# Group_08_alternative.net
KiCad netlist of a schematic drawn in EAGLE
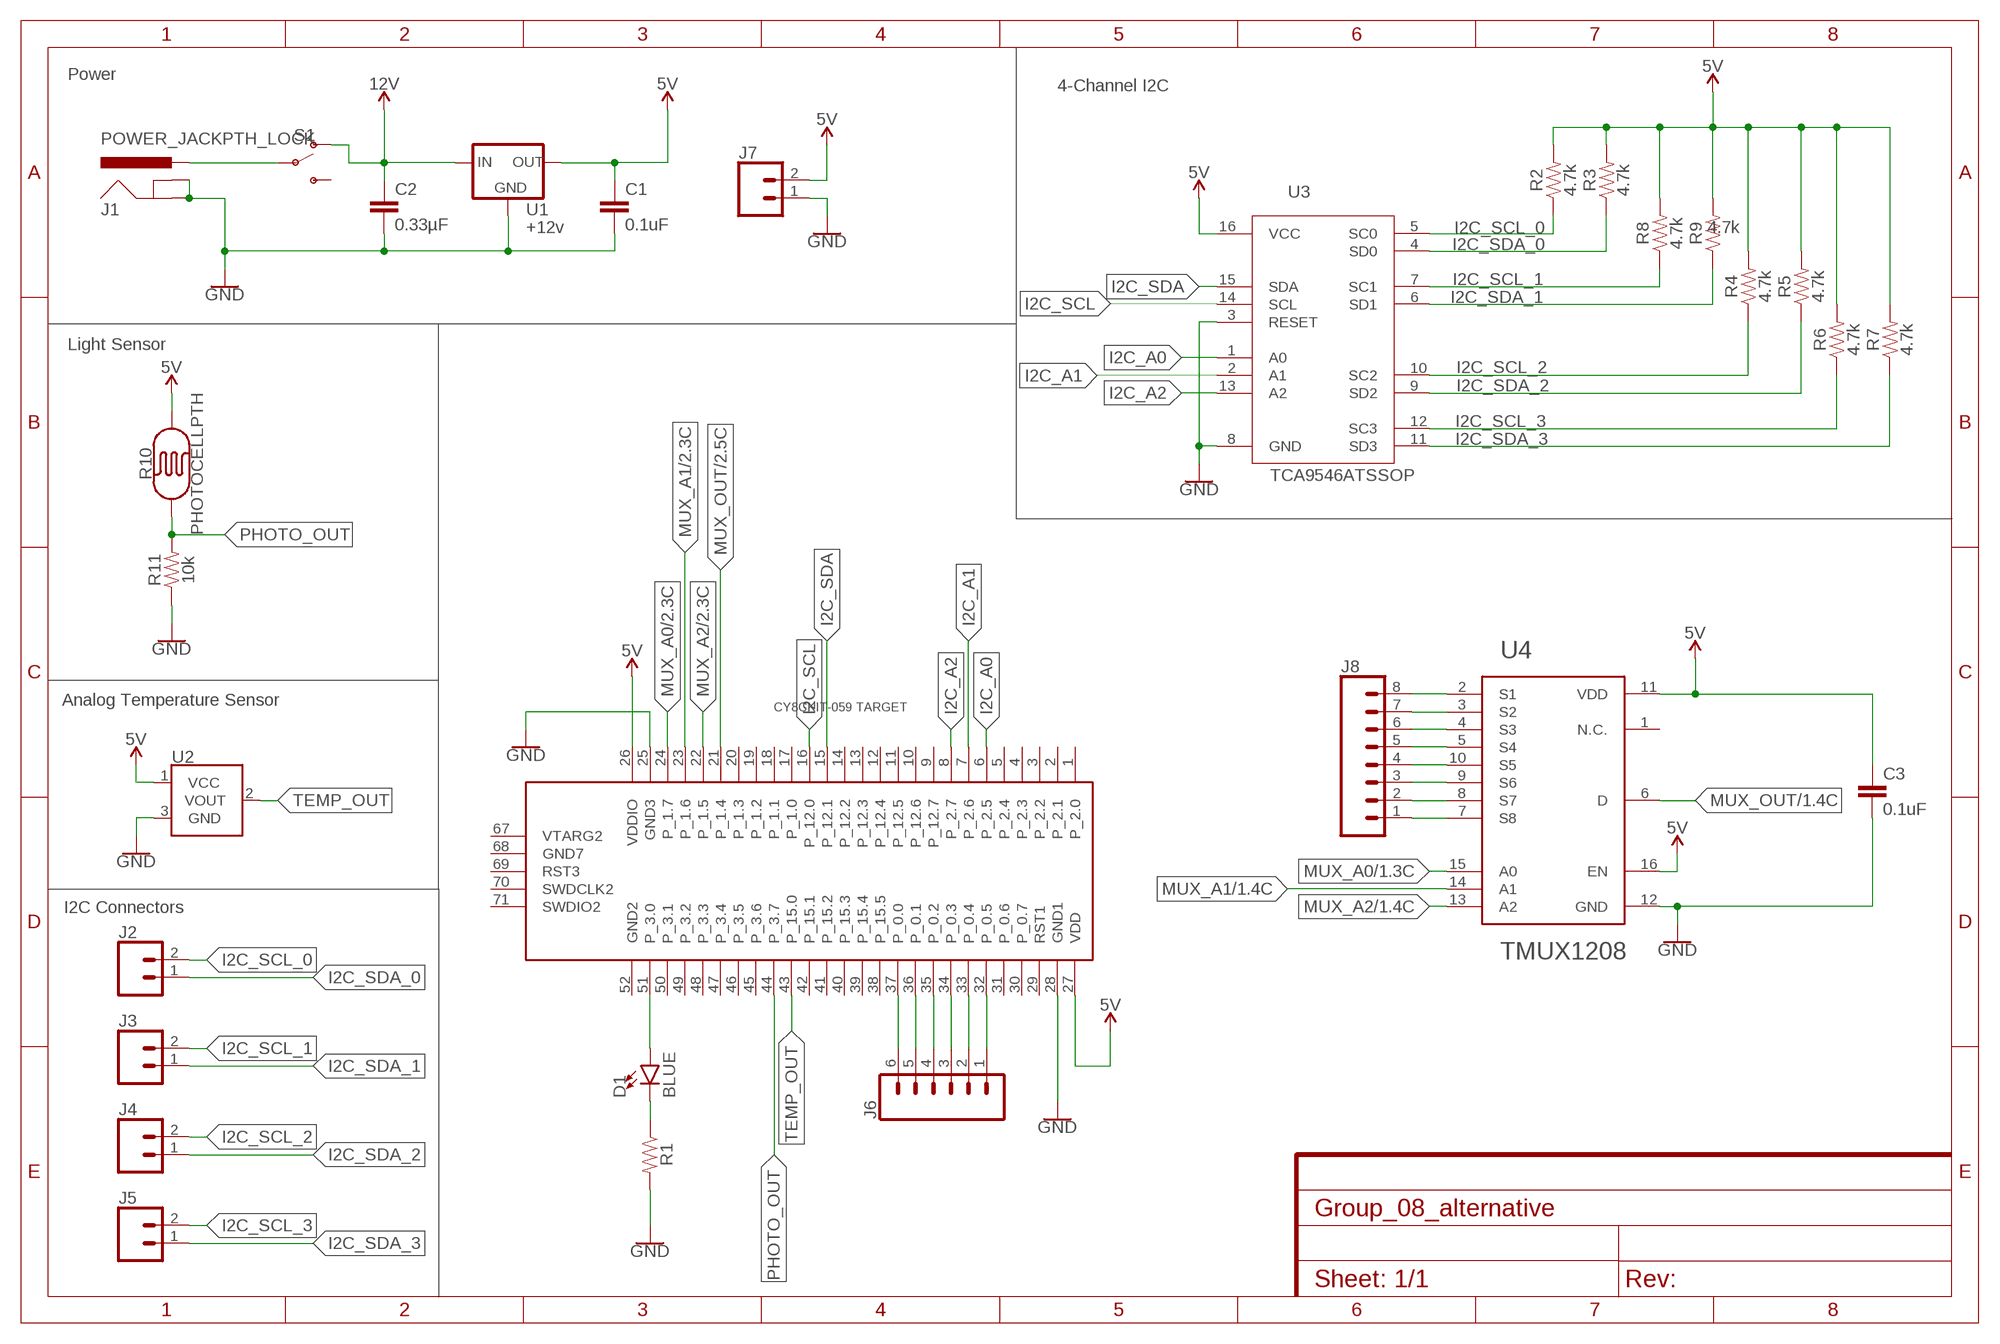
[diagram p0: schematic, sheet 1]

(export (version "E")
  (design (tool "Eeschema 10.0.6"))
  (components
    (comp (ref "C1")
      (value "0.1uF")
      (footprint "eagle-import:CAP-PTH-SMALL-KIT")
      (libsource (lib "eagle-import") (part "0.1UF-KIT-EZ-50V-20%"))
    )
    (comp (ref "C2")
      (value "0.33µF")
      (footprint "eagle-import:0805")
      (libsource (lib "eagle-import") (part "0.33UF/330NF-0805-50V-10%"))
    )
    (comp (ref "C3")
      (value "0.1uF")
      (footprint "eagle-import:CAP-PTH-SMALL-KIT")
      (libsource (lib "eagle-import") (part "0.1UF-KIT-EZ-50V-20%"))
    )
    (comp (ref "CY8CKIT059-TARGET")
      (value "CY8CKIT-059_TARGET")
      (footprint "eagle-import:CY8CKIT-059_TARGET")
      (libsource (lib "eagle-import") (part "CY8CKIT-059_TARGET"))
    )
    (comp (ref "D1")
      (value "BLUE")
      (footprint "eagle-import:LED-1206")
      (libsource (lib "eagle-import") (part "LED-BLUE1206"))
    )
    (comp (ref "J1")
      (value "POWER_JACKPTH_LOCK")
      (footprint "eagle-import:POWER_JACK_PTH_LOCK")
      (libsource (lib "eagle-import") (part "POWER_JACKPTH_LOCK"))
    )
    (comp (ref "J2")
      (value "CONN_02")
      (footprint "eagle-import:1X02")
      (libsource (lib "eagle-import") (part "CONN_02"))
    )
    (comp (ref "J3")
      (value "CONN_02")
      (footprint "eagle-import:1X02")
      (libsource (lib "eagle-import") (part "CONN_02"))
    )
    (comp (ref "J4")
      (value "CONN_02")
      (footprint "eagle-import:1X02")
      (libsource (lib "eagle-import") (part "CONN_02"))
    )
    (comp (ref "J5")
      (value "CONN_02")
      (footprint "eagle-import:1X02")
      (libsource (lib "eagle-import") (part "CONN_02"))
    )
    (comp (ref "J6")
      (value "CONN_06LOCK")
      (footprint "eagle-import:1X06_LOCK")
      (libsource (lib "eagle-import") (part "CONN_06LOCK"))
    )
    (comp (ref "J7")
      (value "CONN_02")
      (footprint "eagle-import:1X02")
      (libsource (lib "eagle-import") (part "CONN_02"))
    )
    (comp (ref "J8")
      (value "CONN_08LOCK")
      (footprint "eagle-import:1X08_LOCK")
      (libsource (lib "eagle-import") (part "CONN_08LOCK"))
    )
    (comp (ref "R1")
      (value "RESISTORAXIAL-0.3")
      (footprint "eagle-import:AXIAL-0.3")
      (libsource (lib "eagle-import") (part "RESISTORAXIAL-0.3"))
    )
    (comp (ref "R2")
      (value "4.7k")
      (footprint "eagle-import:0603")
      (libsource (lib "eagle-import") (part "4.7KOHM-0603-1/10W-1%"))
    )
    (comp (ref "R3")
      (value "4.7k")
      (footprint "eagle-import:0603")
      (libsource (lib "eagle-import") (part "4.7KOHM-0603-1/10W-1%"))
    )
    (comp (ref "R4")
      (value "4.7k")
      (footprint "eagle-import:0603")
      (libsource (lib "eagle-import") (part "4.7KOHM-0603-1/10W-1%"))
    )
    (comp (ref "R5")
      (value "4.7k")
      (footprint "eagle-import:0603")
      (libsource (lib "eagle-import") (part "4.7KOHM-0603-1/10W-1%"))
    )
    (comp (ref "R6")
      (value "4.7k")
      (footprint "eagle-import:0603")
      (libsource (lib "eagle-import") (part "4.7KOHM-0603-1/10W-1%"))
    )
    (comp (ref "R7")
      (value "4.7k")
      (footprint "eagle-import:0603")
      (libsource (lib "eagle-import") (part "4.7KOHM-0603-1/10W-1%"))
    )
    (comp (ref "R8")
      (value "4.7k")
      (footprint "eagle-import:0603")
      (libsource (lib "eagle-import") (part "4.7KOHM-0603-1/10W-1%"))
    )
    (comp (ref "R9")
      (value "4.7k")
      (footprint "eagle-import:0603")
      (libsource (lib "eagle-import") (part "4.7KOHM-0603-1/10W-1%"))
    )
    (comp (ref "R10")
      (value "PHOTOCELLPTH")
      (footprint "eagle-import:PHOTOCELL")
      (libsource (lib "eagle-import") (part "PHOTOCELLPTH"))
    )
    (comp (ref "R11")
      (value "10k")
      (footprint "eagle-import:0603")
      (libsource (lib "eagle-import") (part "10KOHM-0603-1/10W-1%"))
    )
    (comp (ref "S1")
      (value "SWITCH-SPDT-PTH-11.6X4.0MM")
      (footprint "eagle-import:SWITCH_SPDT_PTH_11.6X4.0MM")
      (libsource (lib "eagle-import") (part "SWITCH-SPDT-PTH-11.6X4.0MM"))
    )
    (comp (ref "U1")
      (value "+12v")
      (footprint "eagle-import:TO-252")
      (libsource (lib "eagle-import") (part "V_REG_78XX7812"))
    )
    (comp (ref "U2")
      (value "TMP36GT9")
      (footprint "eagle-import:TO-92")
      (libsource (lib "eagle-import") (part "TMP36GT9"))
    )
    (comp (ref "U3")
      (value "TCA9546ATSSOP")
      (footprint "eagle-import:TSSOP16")
      (libsource (lib "eagle-import") (part "TCA9546ATSSOP"))
    )
    (comp (ref "U4")
      (value "TMUX1208")
      (footprint "eagle-import:QFN16")
      (libsource (lib "eagle-import") (part "TMUX1208"))
    )
  )
  (nets
    (net (code "1") (name "5V") (class "Default")
      (node (ref "C1") (pin "1") (pinfunction "1_1") (pintype "passive"))
      (node (ref "C3") (pin "1") (pinfunction "1_1") (pintype "passive"))
      (node (ref "CY8CKIT059-TARGET") (pin "26") (pinfunction "VDDIO_26") (pintype "bidirectional"))
      (node (ref "CY8CKIT059-TARGET") (pin "27") (pinfunction "VDD_27") (pintype "bidirectional"))
      (node (ref "J7") (pin "2") (pinfunction "2_2") (pintype "passive"))
      (node (ref "R10") (pin "2") (pinfunction "P$2_2") (pintype "bidirectional"))
      (node (ref "R2") (pin "2") (pinfunction "2_2") (pintype "passive"))
      (node (ref "R3") (pin "2") (pinfunction "2_2") (pintype "passive"))
      (node (ref "R4") (pin "2") (pinfunction "2_2") (pintype "passive"))
      (node (ref "R5") (pin "2") (pinfunction "2_2") (pintype "passive"))
      (node (ref "R6") (pin "2") (pinfunction "2_2") (pintype "passive"))
      (node (ref "R7") (pin "2") (pinfunction "2_2") (pintype "passive"))
      (node (ref "R8") (pin "2") (pinfunction "2_2") (pintype "passive"))
      (node (ref "R9") (pin "2") (pinfunction "2_2") (pintype "passive"))
      (node (ref "U1") (pin "2") (pinfunction "OUT_2") (pintype "passive"))
      (node (ref "U2") (pin "1") (pinfunction "VCC_1") (pintype "bidirectional"))
      (node (ref "U3") (pin "16") (pinfunction "VCC_16") (pintype "bidirectional"))
      (node (ref "U4") (pin "11") (pinfunction "VDD_11") (pintype "bidirectional"))
      (node (ref "U4") (pin "16") (pinfunction "EN_16") (pintype "bidirectional"))
    )
    (net (code "2") (name "12V") (class "Default")
      (node (ref "C2") (pin "1") (pinfunction "1_1") (pintype "passive"))
      (node (ref "S1") (pin "1") (pinfunction "O_1") (pintype "passive"))
      (node (ref "U1") (pin "1") (pinfunction "IN_1") (pintype "input"))
    )
    (net (code "3") (name "GND") (class "Default")
      (node (ref "C1") (pin "2") (pinfunction "2_2") (pintype "passive"))
      (node (ref "C2") (pin "2") (pinfunction "2_2") (pintype "passive"))
      (node (ref "C3") (pin "2") (pinfunction "2_2") (pintype "passive"))
      (node (ref "CY8CKIT059-TARGET") (pin "25") (pinfunction "GND3_25") (pintype "bidirectional"))
      (node (ref "CY8CKIT059-TARGET") (pin "28") (pinfunction "GND1_28") (pintype "bidirectional"))
      (node (ref "J1") (pin "GND") (pinfunction "GND_GND") (pintype "bidirectional"))
      (node (ref "J1") (pin "GNDBREAK") (pinfunction "GNDBREAK_GNDBREAK") (pintype "bidirectional"))
      (node (ref "J7") (pin "1") (pinfunction "1_1") (pintype "passive"))
      (node (ref "R1") (pin "P$2") (pinfunction "2_P$2") (pintype "passive"))
      (node (ref "R11") (pin "1") (pinfunction "1_1") (pintype "passive"))
      (node (ref "U1") (pin "3") (pinfunction "GND_3") (pintype "input"))
      (node (ref "U2") (pin "3") (pinfunction "GND_3") (pintype "bidirectional"))
      (node (ref "U3") (pin "3") (pinfunction "RESET_3") (pintype "bidirectional"))
      (node (ref "U3") (pin "8") (pinfunction "GND_8") (pintype "bidirectional"))
      (node (ref "U4") (pin "12") (pinfunction "GND_12") (pintype "bidirectional"))
    )
    (net (code "4") (name "I2C_A0") (class "Default")
      (node (ref "CY8CKIT059-TARGET") (pin "6") (pinfunction "P_2.5_6") (pintype "bidirectional"))
      (node (ref "U3") (pin "1") (pinfunction "A0_1") (pintype "bidirectional"))
    )
    (net (code "5") (name "I2C_A1") (class "Default")
      (node (ref "CY8CKIT059-TARGET") (pin "7") (pinfunction "P_2.6_7") (pintype "bidirectional"))
      (node (ref "U3") (pin "2") (pinfunction "A1_2") (pintype "bidirectional"))
    )
    (net (code "6") (name "I2C_A2") (class "Default")
      (node (ref "CY8CKIT059-TARGET") (pin "8") (pinfunction "P_2.7_8") (pintype "bidirectional"))
      (node (ref "U3") (pin "13") (pinfunction "A2_13") (pintype "bidirectional"))
    )
    (net (code "7") (name "I2C_SCL") (class "Default")
      (node (ref "CY8CKIT059-TARGET") (pin "16") (pinfunction "P_12.0_16") (pintype "bidirectional"))
      (node (ref "U3") (pin "14") (pinfunction "SCL_14") (pintype "bidirectional"))
    )
    (net (code "8") (name "I2C_SCL_0") (class "Default")
      (node (ref "J2") (pin "2") (pinfunction "2_2") (pintype "passive"))
      (node (ref "R2") (pin "1") (pinfunction "1_1") (pintype "passive"))
      (node (ref "U3") (pin "5") (pinfunction "SC0_5") (pintype "bidirectional"))
    )
    (net (code "9") (name "I2C_SCL_1") (class "Default")
      (node (ref "J3") (pin "2") (pinfunction "2_2") (pintype "passive"))
      (node (ref "R8") (pin "1") (pinfunction "1_1") (pintype "passive"))
      (node (ref "U3") (pin "7") (pinfunction "SC1_7") (pintype "bidirectional"))
    )
    (net (code "10") (name "I2C_SCL_2") (class "Default")
      (node (ref "J4") (pin "2") (pinfunction "2_2") (pintype "passive"))
      (node (ref "R4") (pin "1") (pinfunction "1_1") (pintype "passive"))
      (node (ref "U3") (pin "10") (pinfunction "SC2_10") (pintype "bidirectional"))
    )
    (net (code "11") (name "I2C_SCL_3") (class "Default")
      (node (ref "J5") (pin "2") (pinfunction "2_2") (pintype "passive"))
      (node (ref "R6") (pin "1") (pinfunction "1_1") (pintype "passive"))
      (node (ref "U3") (pin "12") (pinfunction "SC3_12") (pintype "bidirectional"))
    )
    (net (code "12") (name "I2C_SDA") (class "Default")
      (node (ref "CY8CKIT059-TARGET") (pin "15") (pinfunction "P_12.1_15") (pintype "bidirectional"))
      (node (ref "U3") (pin "15") (pinfunction "SDA_15") (pintype "bidirectional"))
    )
    (net (code "13") (name "I2C_SDA_0") (class "Default")
      (node (ref "J2") (pin "1") (pinfunction "1_1") (pintype "passive"))
      (node (ref "R3") (pin "1") (pinfunction "1_1") (pintype "passive"))
      (node (ref "U3") (pin "4") (pinfunction "SD0_4") (pintype "bidirectional"))
    )
    (net (code "14") (name "I2C_SDA_1") (class "Default")
      (node (ref "J3") (pin "1") (pinfunction "1_1") (pintype "passive"))
      (node (ref "R9") (pin "1") (pinfunction "1_1") (pintype "passive"))
      (node (ref "U3") (pin "6") (pinfunction "SD1_6") (pintype "bidirectional"))
    )
    (net (code "15") (name "I2C_SDA_2") (class "Default")
      (node (ref "J4") (pin "1") (pinfunction "1_1") (pintype "passive"))
      (node (ref "R5") (pin "1") (pinfunction "1_1") (pintype "passive"))
      (node (ref "U3") (pin "9") (pinfunction "SD2_9") (pintype "bidirectional"))
    )
    (net (code "16") (name "I2C_SDA_3") (class "Default")
      (node (ref "J5") (pin "1") (pinfunction "1_1") (pintype "passive"))
      (node (ref "R7") (pin "1") (pinfunction "1_1") (pintype "passive"))
      (node (ref "U3") (pin "11") (pinfunction "SD3_11") (pintype "bidirectional"))
    )
    (net (code "17") (name "MUX_A0{slash}1.3C") (class "Default")
      (node (ref "U4") (pin "15") (pinfunction "A0_15") (pintype "bidirectional"))
    )
    (net (code "18") (name "MUX_A0{slash}2.3C") (class "Default")
      (node (ref "CY8CKIT059-TARGET") (pin "24") (pinfunction "P_1.7_24") (pintype "bidirectional"))
    )
    (net (code "19") (name "MUX_A1{slash}1.4C") (class "Default")
      (node (ref "U4") (pin "14") (pinfunction "A1_14") (pintype "bidirectional"))
    )
    (net (code "20") (name "MUX_A1{slash}2.3C") (class "Default")
      (node (ref "CY8CKIT059-TARGET") (pin "23") (pinfunction "P_1.6_23") (pintype "bidirectional"))
    )
    (net (code "21") (name "MUX_A2{slash}1.4C") (class "Default")
      (node (ref "U4") (pin "13") (pinfunction "A2_13") (pintype "bidirectional"))
    )
    (net (code "22") (name "MUX_A2{slash}2.3C") (class "Default")
      (node (ref "CY8CKIT059-TARGET") (pin "22") (pinfunction "P_1.5_22") (pintype "bidirectional"))
    )
    (net (code "23") (name "MUX_OUT{slash}1.4C") (class "Default")
      (node (ref "U4") (pin "6") (pinfunction "D_6") (pintype "bidirectional"))
    )
    (net (code "24") (name "MUX_OUT{slash}2.5C") (class "Default")
      (node (ref "CY8CKIT059-TARGET") (pin "21") (pinfunction "P_1.4_21") (pintype "bidirectional"))
    )
    (net (code "25") (name "Net-(CY8CKIT059-TARGET-P_0.0)") (class "Default")
      (node (ref "CY8CKIT059-TARGET") (pin "37") (pinfunction "P_0.0_37") (pintype "bidirectional"))
      (node (ref "J6") (pin "6") (pinfunction "6_6") (pintype "passive"))
    )
    (net (code "26") (name "Net-(CY8CKIT059-TARGET-P_0.1)") (class "Default")
      (node (ref "CY8CKIT059-TARGET") (pin "36") (pinfunction "P_0.1_36") (pintype "bidirectional"))
      (node (ref "J6") (pin "5") (pinfunction "5_5") (pintype "passive"))
    )
    (net (code "27") (name "Net-(CY8CKIT059-TARGET-P_0.2)") (class "Default")
      (node (ref "CY8CKIT059-TARGET") (pin "35") (pinfunction "P_0.2_35") (pintype "bidirectional"))
      (node (ref "J6") (pin "4") (pinfunction "4_4") (pintype "passive"))
    )
    (net (code "28") (name "Net-(CY8CKIT059-TARGET-P_0.3)") (class "Default")
      (node (ref "CY8CKIT059-TARGET") (pin "34") (pinfunction "P_0.3_34") (pintype "bidirectional"))
      (node (ref "J6") (pin "3") (pinfunction "3_3") (pintype "passive"))
    )
    (net (code "29") (name "Net-(CY8CKIT059-TARGET-P_0.4)") (class "Default")
      (node (ref "CY8CKIT059-TARGET") (pin "33") (pinfunction "P_0.4_33") (pintype "bidirectional"))
      (node (ref "J6") (pin "2") (pinfunction "2_2") (pintype "passive"))
    )
    (net (code "30") (name "Net-(CY8CKIT059-TARGET-P_0.5)") (class "Default")
      (node (ref "CY8CKIT059-TARGET") (pin "32") (pinfunction "P_0.5_32") (pintype "bidirectional"))
      (node (ref "J6") (pin "1") (pinfunction "1_1") (pintype "passive"))
    )
    (net (code "31") (name "Net-(CY8CKIT059-TARGET-P_3.0)") (class "Default")
      (node (ref "CY8CKIT059-TARGET") (pin "51") (pinfunction "P_3.0_51") (pintype "bidirectional"))
      (node (ref "D1") (pin "A") (pinfunction "A_A") (pintype "passive"))
    )
    (net (code "32") (name "Net-(R1-1)") (class "Default")
      (node (ref "D1") (pin "C") (pinfunction "C_C") (pintype "passive"))
      (node (ref "R1") (pin "P$1") (pinfunction "1_P$1") (pintype "passive"))
    )
    (net (code "33") (name "Net-(S1-P)") (class "Default")
      (node (ref "J1") (pin "PWR") (pinfunction "PWR_PWR") (pintype "bidirectional"))
      (node (ref "S1") (pin "2") (pinfunction "P_2") (pintype "passive"))
    )
    (net (code "34") (name "Net-(U4-S1)") (class "Default")
      (node (ref "J8") (pin "8") (pinfunction "8_8") (pintype "passive"))
      (node (ref "U4") (pin "2") (pinfunction "S1_2") (pintype "bidirectional"))
    )
    (net (code "35") (name "Net-(U4-S2)") (class "Default")
      (node (ref "J8") (pin "7") (pinfunction "7_7") (pintype "passive"))
      (node (ref "U4") (pin "3") (pinfunction "S2_3") (pintype "bidirectional"))
    )
    (net (code "36") (name "Net-(U4-S3)") (class "Default")
      (node (ref "J8") (pin "6") (pinfunction "6_6") (pintype "passive"))
      (node (ref "U4") (pin "4") (pinfunction "S3_4") (pintype "bidirectional"))
    )
    (net (code "37") (name "Net-(U4-S4)") (class "Default")
      (node (ref "J8") (pin "5") (pinfunction "5_5") (pintype "passive"))
      (node (ref "U4") (pin "5") (pinfunction "S4_5") (pintype "bidirectional"))
    )
    (net (code "38") (name "Net-(U4-S5)") (class "Default")
      (node (ref "J8") (pin "4") (pinfunction "4_4") (pintype "passive"))
      (node (ref "U4") (pin "10") (pinfunction "S5_10") (pintype "bidirectional"))
    )
    (net (code "39") (name "Net-(U4-S6)") (class "Default")
      (node (ref "J8") (pin "3") (pinfunction "3_3") (pintype "passive"))
      (node (ref "U4") (pin "9") (pinfunction "S6_9") (pintype "bidirectional"))
    )
    (net (code "40") (name "Net-(U4-S7)") (class "Default")
      (node (ref "J8") (pin "2") (pinfunction "2_2") (pintype "passive"))
      (node (ref "U4") (pin "8") (pinfunction "S7_8") (pintype "bidirectional"))
    )
    (net (code "41") (name "Net-(U4-S8)") (class "Default")
      (node (ref "J8") (pin "1") (pinfunction "1_1") (pintype "passive"))
      (node (ref "U4") (pin "7") (pinfunction "S8_7") (pintype "bidirectional"))
    )
    (net (code "42") (name "PHOTO_OUT") (class "Default")
      (node (ref "CY8CKIT059-TARGET") (pin "44") (pinfunction "P_3.7_44") (pintype "bidirectional"))
      (node (ref "R10") (pin "1") (pinfunction "P$1_1") (pintype "bidirectional"))
      (node (ref "R11") (pin "2") (pinfunction "2_2") (pintype "passive"))
    )
    (net (code "43") (name "TEMP_OUT") (class "Default")
      (node (ref "CY8CKIT059-TARGET") (pin "43") (pinfunction "P_15.0_43") (pintype "bidirectional"))
      (node (ref "U2") (pin "2") (pinfunction "VOUT_2") (pintype "bidirectional"))
    )
    (net (code "44") (name "unconnected-(CY8CKIT059-TARGET-GND2-Pad52)") (class "Default")
      (node (ref "CY8CKIT059-TARGET") (pin "52") (pinfunction "GND2_52") (pintype "bidirectional"))
    )
    (net (code "45") (name "unconnected-(CY8CKIT059-TARGET-GND7-Pad68)") (class "Default")
      (node (ref "CY8CKIT059-TARGET") (pin "68") (pinfunction "GND7_68") (pintype "bidirectional"))
    )
    (net (code "46") (name "unconnected-(CY8CKIT059-TARGET-P_0.6-Pad31)") (class "Default")
      (node (ref "CY8CKIT059-TARGET") (pin "31") (pinfunction "P_0.6_31") (pintype "bidirectional"))
    )
    (net (code "47") (name "unconnected-(CY8CKIT059-TARGET-P_0.7-Pad30)") (class "Default")
      (node (ref "CY8CKIT059-TARGET") (pin "30") (pinfunction "P_0.7_30") (pintype "bidirectional"))
    )
    (net (code "48") (name "unconnected-(CY8CKIT059-TARGET-P_1.0-Pad17)") (class "Default")
      (node (ref "CY8CKIT059-TARGET") (pin "17") (pinfunction "P_1.0_17") (pintype "bidirectional"))
    )
    (net (code "49") (name "unconnected-(CY8CKIT059-TARGET-P_1.1-Pad18)") (class "Default")
      (node (ref "CY8CKIT059-TARGET") (pin "18") (pinfunction "P_1.1_18") (pintype "bidirectional"))
    )
    (net (code "50") (name "unconnected-(CY8CKIT059-TARGET-P_1.2-Pad19)") (class "Default")
      (node (ref "CY8CKIT059-TARGET") (pin "19") (pinfunction "P_1.2_19") (pintype "bidirectional"))
    )
    (net (code "51") (name "unconnected-(CY8CKIT059-TARGET-P_1.3-Pad20)") (class "Default")
      (node (ref "CY8CKIT059-TARGET") (pin "20") (pinfunction "P_1.3_20") (pintype "bidirectional"))
    )
    (net (code "52") (name "unconnected-(CY8CKIT059-TARGET-P_2.0-Pad1)") (class "Default")
      (node (ref "CY8CKIT059-TARGET") (pin "1") (pinfunction "P_2.0_1") (pintype "bidirectional"))
    )
    (net (code "53") (name "unconnected-(CY8CKIT059-TARGET-P_2.1-Pad2)") (class "Default")
      (node (ref "CY8CKIT059-TARGET") (pin "2") (pinfunction "P_2.1_2") (pintype "bidirectional"))
    )
    (net (code "54") (name "unconnected-(CY8CKIT059-TARGET-P_2.2-Pad3)") (class "Default")
      (node (ref "CY8CKIT059-TARGET") (pin "3") (pinfunction "P_2.2_3") (pintype "bidirectional"))
    )
    (net (code "55") (name "unconnected-(CY8CKIT059-TARGET-P_2.3-Pad4)") (class "Default")
      (node (ref "CY8CKIT059-TARGET") (pin "4") (pinfunction "P_2.3_4") (pintype "bidirectional"))
    )
    (net (code "56") (name "unconnected-(CY8CKIT059-TARGET-P_2.4-Pad5)") (class "Default")
      (node (ref "CY8CKIT059-TARGET") (pin "5") (pinfunction "P_2.4_5") (pintype "bidirectional"))
    )
    (net (code "57") (name "unconnected-(CY8CKIT059-TARGET-P_3.1-Pad50)") (class "Default")
      (node (ref "CY8CKIT059-TARGET") (pin "50") (pinfunction "P_3.1_50") (pintype "bidirectional"))
    )
    (net (code "58") (name "unconnected-(CY8CKIT059-TARGET-P_3.2-Pad49)") (class "Default")
      (node (ref "CY8CKIT059-TARGET") (pin "49") (pinfunction "P_3.2_49") (pintype "bidirectional"))
    )
    (net (code "59") (name "unconnected-(CY8CKIT059-TARGET-P_3.3-Pad48)") (class "Default")
      (node (ref "CY8CKIT059-TARGET") (pin "48") (pinfunction "P_3.3_48") (pintype "bidirectional"))
    )
    (net (code "60") (name "unconnected-(CY8CKIT059-TARGET-P_3.4-Pad47)") (class "Default")
      (node (ref "CY8CKIT059-TARGET") (pin "47") (pinfunction "P_3.4_47") (pintype "bidirectional"))
    )
    (net (code "61") (name "unconnected-(CY8CKIT059-TARGET-P_3.5-Pad46)") (class "Default")
      (node (ref "CY8CKIT059-TARGET") (pin "46") (pinfunction "P_3.5_46") (pintype "bidirectional"))
    )
    (net (code "62") (name "unconnected-(CY8CKIT059-TARGET-P_3.6-Pad45)") (class "Default")
      (node (ref "CY8CKIT059-TARGET") (pin "45") (pinfunction "P_3.6_45") (pintype "bidirectional"))
    )
    (net (code "63") (name "unconnected-(CY8CKIT059-TARGET-P_12.2-Pad14)") (class "Default")
      (node (ref "CY8CKIT059-TARGET") (pin "14") (pinfunction "P_12.2_14") (pintype "bidirectional"))
    )
    (net (code "64") (name "unconnected-(CY8CKIT059-TARGET-P_12.3-Pad13)") (class "Default")
      (node (ref "CY8CKIT059-TARGET") (pin "13") (pinfunction "P_12.3_13") (pintype "bidirectional"))
    )
    (net (code "65") (name "unconnected-(CY8CKIT059-TARGET-P_12.4-Pad12)") (class "Default")
      (node (ref "CY8CKIT059-TARGET") (pin "12") (pinfunction "P_12.4_12") (pintype "bidirectional"))
    )
    (net (code "66") (name "unconnected-(CY8CKIT059-TARGET-P_12.5-Pad11)") (class "Default")
      (node (ref "CY8CKIT059-TARGET") (pin "11") (pinfunction "P_12.5_11") (pintype "bidirectional"))
    )
    (net (code "67") (name "unconnected-(CY8CKIT059-TARGET-P_12.6-Pad10)") (class "Default")
      (node (ref "CY8CKIT059-TARGET") (pin "10") (pinfunction "P_12.6_10") (pintype "bidirectional"))
    )
    (net (code "68") (name "unconnected-(CY8CKIT059-TARGET-P_12.7-Pad9)") (class "Default")
      (node (ref "CY8CKIT059-TARGET") (pin "9") (pinfunction "P_12.7_9") (pintype "bidirectional"))
    )
    (net (code "69") (name "unconnected-(CY8CKIT059-TARGET-P_15.1-Pad42)") (class "Default")
      (node (ref "CY8CKIT059-TARGET") (pin "42") (pinfunction "P_15.1_42") (pintype "bidirectional"))
    )
    (net (code "70") (name "unconnected-(CY8CKIT059-TARGET-P_15.2-Pad41)") (class "Default")
      (node (ref "CY8CKIT059-TARGET") (pin "41") (pinfunction "P_15.2_41") (pintype "bidirectional"))
    )
    (net (code "71") (name "unconnected-(CY8CKIT059-TARGET-P_15.3-Pad40)") (class "Default")
      (node (ref "CY8CKIT059-TARGET") (pin "40") (pinfunction "P_15.3_40") (pintype "bidirectional"))
    )
    (net (code "72") (name "unconnected-(CY8CKIT059-TARGET-P_15.4-Pad39)") (class "Default")
      (node (ref "CY8CKIT059-TARGET") (pin "39") (pinfunction "P_15.4_39") (pintype "bidirectional"))
    )
    (net (code "73") (name "unconnected-(CY8CKIT059-TARGET-P_15.5-Pad38)") (class "Default")
      (node (ref "CY8CKIT059-TARGET") (pin "38") (pinfunction "P_15.5_38") (pintype "bidirectional"))
    )
    (net (code "74") (name "unconnected-(CY8CKIT059-TARGET-RST1-Pad29)") (class "Default")
      (node (ref "CY8CKIT059-TARGET") (pin "29") (pinfunction "RST1_29") (pintype "bidirectional"))
    )
    (net (code "75") (name "unconnected-(CY8CKIT059-TARGET-RST3-Pad69)") (class "Default")
      (node (ref "CY8CKIT059-TARGET") (pin "69") (pinfunction "RST3_69") (pintype "bidirectional"))
    )
    (net (code "76") (name "unconnected-(CY8CKIT059-TARGET-SWDCLK2-Pad70)") (class "Default")
      (node (ref "CY8CKIT059-TARGET") (pin "70") (pinfunction "SWDCLK2_70") (pintype "bidirectional"))
    )
    (net (code "77") (name "unconnected-(CY8CKIT059-TARGET-SWDIO2-Pad71)") (class "Default")
      (node (ref "CY8CKIT059-TARGET") (pin "71") (pinfunction "SWDIO2_71") (pintype "bidirectional"))
    )
    (net (code "78") (name "unconnected-(CY8CKIT059-TARGET-VTARG2-Pad67)") (class "Default")
      (node (ref "CY8CKIT059-TARGET") (pin "67") (pinfunction "VTARG2_67") (pintype "bidirectional"))
    )
    (net (code "79") (name "unconnected-(S1-S-Pad3)") (class "Default")
      (node (ref "S1") (pin "3") (pinfunction "S_3") (pintype "passive"))
    )
    (net (code "80") (name "unconnected-(U4-N.C.-Pad1)") (class "Default")
      (node (ref "U4") (pin "1") (pinfunction "N.C._1") (pintype "bidirectional"))
    )
  )
)
